# iWoofer_V4_03_OT.net
KiCad netlist of a schematic drawn in Altium Designer
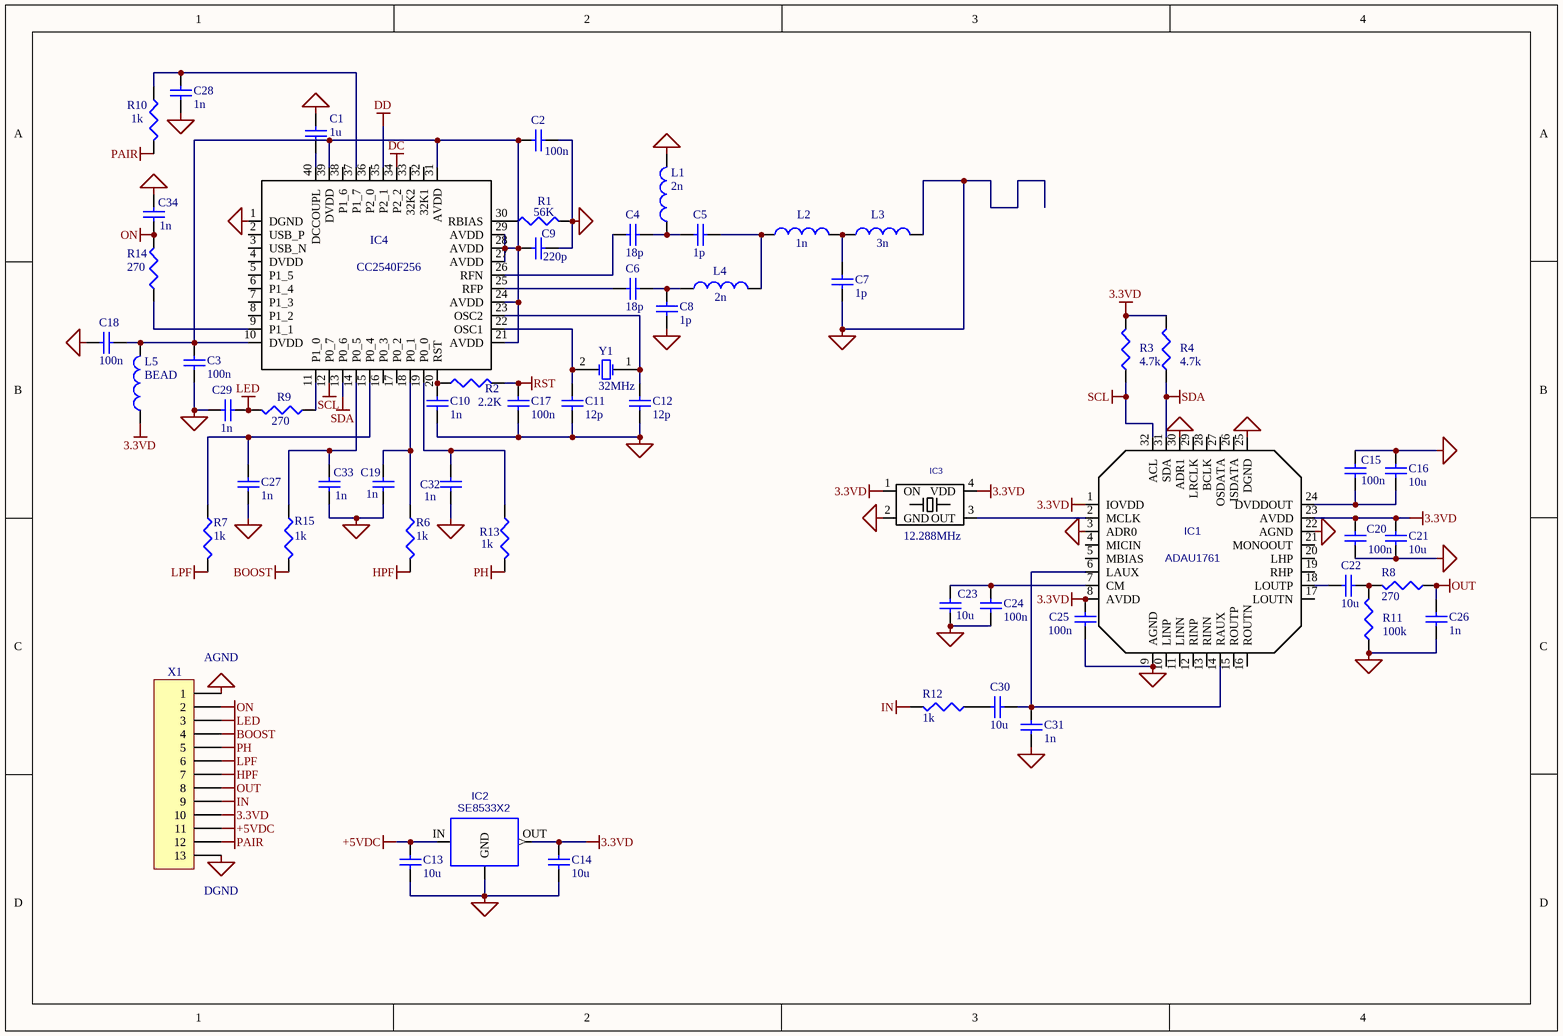
[diagram p0: iWoofer_V4_03_OT.SchDoc]

(export (version "E")
  (design (tool "Eeschema 10.0.6"))
  (components
    (comp (ref "C1")
      (value "1u")
      (footprint "0402C")
      (description "Capacitor")
      (fields (field (name "PUBLISHER") "Altium Limited"))
      (libsource (lib "vic_2") (part "Cap"))
    )
    (comp (ref "C2")
      (value "100n")
      (footprint "0402C")
      (description "Capacitor")
      (fields (field (name "PUBLISHER") "Altium Limited"))
      (libsource (lib "vic_2") (part "Cap"))
    )
    (comp (ref "C3")
      (value "100n")
      (footprint "0402C")
      (description "Capacitor")
      (fields (field (name "PUBLISHER") "Altium Limited"))
      (libsource (lib "vic_2") (part "Cap"))
    )
    (comp (ref "C4")
      (value "18p")
      (footprint "0402C")
      (description "Capacitor NPO")
      (fields (field (name "PUBLISHER") "Altium Limited"))
      (libsource (lib "vic_2") (part "Cap"))
    )
    (comp (ref "C5")
      (value "1p")
      (footprint "0402C")
      (description "Capacitor NPO")
      (fields (field (name "PUBLISHER") "Altium Limited"))
      (libsource (lib "vic_2") (part "Cap"))
    )
    (comp (ref "C6")
      (value "18p")
      (footprint "0402C")
      (description "Capacitor NPO")
      (fields (field (name "PUBLISHER") "Altium Limited"))
      (libsource (lib "vic_2") (part "Cap"))
    )
    (comp (ref "C7")
      (value "1p")
      (footprint "0402C")
      (description "Capacitor NPO")
      (fields (field (name "PUBLISHER") "Altium Limited"))
      (libsource (lib "vic_2") (part "Cap"))
    )
    (comp (ref "C8")
      (value "1p")
      (footprint "0402C")
      (description "Capacitor NPO")
      (fields (field (name "PUBLISHER") "Altium Limited"))
      (libsource (lib "vic_2") (part "Cap"))
    )
    (comp (ref "C9")
      (value "220p")
      (footprint "0402C")
      (description "Capacitor NPO")
      (fields (field (name "PUBLISHER") "Altium Limited"))
      (libsource (lib "vic_2") (part "Cap"))
    )
    (comp (ref "C10")
      (value "1n")
      (footprint "0402C")
      (description "Capacitor")
      (fields (field (name "PUBLISHER") "Altium Limited"))
      (libsource (lib "vic_2") (part "Cap"))
    )
    (comp (ref "C11")
      (value "12p")
      (footprint "0402C")
      (description "Capacitor NPO")
      (fields (field (name "PUBLISHER") "Altium Limited"))
      (libsource (lib "vic_2") (part "Cap"))
    )
    (comp (ref "C12")
      (value "12p")
      (footprint "0402C")
      (description "Capacitor NPO")
      (fields (field (name "PUBLISHER") "Altium Limited"))
      (libsource (lib "vic_2") (part "Cap"))
    )
    (comp (ref "C13")
      (value "10u")
      (footprint "0805C")
      (description "CL21A476MQMNRN or analog")
      (fields (field (name "PUBLISHER") "Altium Limited"))
      (libsource (lib "vic_2") (part "Cap"))
    )
    (comp (ref "C14")
      (value "10u")
      (footprint "0805C")
      (description "CL21A476MQMNRN or analog")
      (fields (field (name "PUBLISHER") "Altium Limited"))
      (libsource (lib "vic_2") (part "Cap"))
    )
    (comp (ref "C15")
      (value "100n")
      (footprint "0402C")
      (description "Capacitor")
      (fields (field (name "PUBLISHER") "Altium Limited"))
      (libsource (lib "vic_2") (part "Cap"))
    )
    (comp (ref "C16")
      (value "10u")
      (footprint "0805C")
      (description "CL21A476MQMNRN or analog")
      (fields (field (name "PUBLISHER") "Altium Limited"))
      (libsource (lib "vic_2") (part "Cap"))
    )
    (comp (ref "C17")
      (value "100n")
      (footprint "0402C")
      (description "Capacitor")
      (fields (field (name "PUBLISHER") "Altium Limited"))
      (libsource (lib "vic_2") (part "Cap"))
    )
    (comp (ref "C18")
      (value "100n")
      (footprint "0402C")
      (description "Capacitor")
      (fields (field (name "PUBLISHER") "Altium Limited"))
      (libsource (lib "vic_2") (part "Cap"))
    )
    (comp (ref "C19")
      (value "1n")
      (footprint "0402C")
      (description "Capacitor")
      (fields (field (name "PUBLISHER") "Altium Limited"))
      (libsource (lib "vic_2") (part "Cap"))
    )
    (comp (ref "C20")
      (value "100n")
      (footprint "0402C")
      (description "Capacitor")
      (fields (field (name "PUBLISHER") "Altium Limited"))
      (libsource (lib "vic_2") (part "Cap"))
    )
    (comp (ref "C21")
      (value "10u")
      (footprint "0805C")
      (description "CL21A476MQMNRN or analog")
      (fields (field (name "PUBLISHER") "Altium Limited"))
      (libsource (lib "vic_2") (part "Cap"))
    )
    (comp (ref "C22")
      (value "10u")
      (footprint "0805C")
      (description "CL21A476MQMNRN or analog")
      (fields (field (name "PUBLISHER") "Altium Limited"))
      (libsource (lib "vic_2") (part "Cap"))
    )
    (comp (ref "C23")
      (value "10u")
      (footprint "0805C")
      (description "CL21A476MQMNRN or analog")
      (fields (field (name "PUBLISHER") "Altium Limited"))
      (libsource (lib "vic_2") (part "Cap"))
    )
    (comp (ref "C24")
      (value "100n")
      (footprint "0402C")
      (description "Capacitor")
      (fields (field (name "PUBLISHER") "Altium Limited"))
      (libsource (lib "vic_2") (part "Cap"))
    )
    (comp (ref "C25")
      (value "100n")
      (footprint "0603")
      (description "Capacitor")
      (fields (field (name "PUBLISHER") "Altium Limited"))
      (libsource (lib "vic_2") (part "Cap"))
    )
    (comp (ref "C26")
      (value "1n")
      (footprint "0402C")
      (description "Capacitor")
      (fields (field (name "PUBLISHER") "Altium Limited"))
      (libsource (lib "vic_2") (part "Cap"))
    )
    (comp (ref "C27")
      (value "1n")
      (footprint "0402C")
      (description "Capacitor")
      (fields (field (name "PUBLISHER") "Altium Limited"))
      (libsource (lib "vic_2") (part "Cap"))
    )
    (comp (ref "C28")
      (value "1n")
      (footprint "0402C")
      (description "Capacitor")
      (fields (field (name "PUBLISHER") "Altium Limited"))
      (libsource (lib "vic_2") (part "Cap"))
    )
    (comp (ref "C29")
      (value "1n")
      (footprint "0402C")
      (description "Capacitor")
      (fields (field (name "PUBLISHER") "Altium Limited"))
      (libsource (lib "vic_2") (part "Cap"))
    )
    (comp (ref "C30")
      (value "10u")
      (footprint "0805C")
      (description "CL21A476MQMNRN or analog")
      (fields (field (name "PUBLISHER") "Altium Limited"))
      (libsource (lib "vic_2") (part "Cap"))
    )
    (comp (ref "C31")
      (value "1n")
      (footprint "0402C")
      (description "Capacitor")
      (fields (field (name "PUBLISHER") "Altium Limited"))
      (libsource (lib "vic_2") (part "Cap"))
    )
    (comp (ref "C32")
      (value "1n")
      (footprint "0402C")
      (description "Capacitor")
      (fields (field (name "PUBLISHER") "Altium Limited"))
      (libsource (lib "vic_2") (part "Cap"))
    )
    (comp (ref "C33")
      (value "1n")
      (footprint "0402C")
      (description "Capacitor")
      (fields (field (name "PUBLISHER") "Altium Limited"))
      (libsource (lib "vic_2") (part "Cap"))
    )
    (comp (ref "C34")
      (value "1n")
      (footprint "0402C")
      (description "Capacitor")
      (fields (field (name "PUBLISHER") "Altium Limited"))
      (libsource (lib "vic_2") (part "Cap"))
    )
    (comp (ref "IC1")
      (value "ADAU1761")
      (footprint "ADAU1761_long")
      (description "DSP")
      (libsource (lib "1") (part "ADAU1761"))
    )
    (comp (ref "IC2")
      (value "SE8533X2")
      (footprint "SOT-23_BC807-40(Primary)")
      (description "REGULATOR")
      (libsource (lib "1") (part "78L05"))
    )
    (comp (ref "IC3")
      (value "12.288 MHz")
      (footprint "OSC_3225")
      (description "12.288 MHz Oscillator 5032 case")
      (libsource (lib "1") (part "YSO 321SR"))
    )
    (comp (ref "IC4")
      (value "CC2540F256")
      (footprint "cc2540 TOP")
      (description "cc2540f256")
      (libsource (lib "1") (part "CC2540"))
    )
    (comp (ref "L1")
      (value "2n")
      (footprint "0402L")
      (description "HBLS1005-2N0S")
      (fields (field (name "PUBLISHER") "Altium Limited"))
      (libsource (lib "Miscellaneous Devices") (part "Inductor"))
    )
    (comp (ref "L2")
      (value "1n")
      (footprint "0402L")
      (description "HBLS1005-1N0S")
      (fields (field (name "PUBLISHER") "Altium Limited"))
      (libsource (lib "Miscellaneous Devices") (part "Inductor"))
    )
    (comp (ref "L3")
      (value "3n")
      (footprint "0402L")
      (description "HBLS1005-3N0S")
      (fields (field (name "PUBLISHER") "Altium Limited"))
      (libsource (lib "Miscellaneous Devices") (part "Inductor"))
    )
    (comp (ref "L4")
      (value "2n")
      (footprint "0402L")
      (description "HBLS1005-2N0S")
      (fields (field (name "PUBLISHER") "Altium Limited"))
      (libsource (lib "Miscellaneous Devices") (part "Inductor"))
    )
    (comp (ref "L5")
      (value "BEAD")
      (footprint "0402L")
      (description "bead 200@100MHz")
      (fields (field (name "PUBLISHER") "Altium Limited"))
      (libsource (lib "Miscellaneous Devices") (part "Inductor"))
    )
    (comp (ref "R1")
      (value "56K")
      (footprint "0402R")
      (description "Resistor")
      (fields (field (name "PUBLISHER") "Altium Limited"))
      (libsource (lib "vic_2") (part "Res3"))
    )
    (comp (ref "R2")
      (value "2.2K")
      (footprint "0402R")
      (description "Resistor")
      (fields (field (name "PUBLISHER") "Altium Limited"))
      (libsource (lib "vic_2") (part "Res3"))
    )
    (comp (ref "R3")
      (value "4.7k")
      (footprint "0402R")
      (description "Resistor")
      (fields (field (name "PUBLISHER") "Altium Limited"))
      (libsource (lib "vic_2") (part "Res3"))
    )
    (comp (ref "R4")
      (value "4.7k")
      (footprint "0402R")
      (description "Resistor")
      (fields (field (name "PUBLISHER") "Altium Limited"))
      (libsource (lib "vic_2") (part "Res3"))
    )
    (comp (ref "R6")
      (value "1k")
      (footprint "0402R")
      (description "Resistor")
      (fields (field (name "PUBLISHER") "Altium Limited"))
      (libsource (lib "vic_2") (part "Res3"))
    )
    (comp (ref "R7")
      (value "1k")
      (footprint "0402R")
      (description "Resistor")
      (fields (field (name "PUBLISHER") "Altium Limited"))
      (libsource (lib "vic_2") (part "Res3"))
    )
    (comp (ref "R8")
      (value "270")
      (footprint "0402R")
      (description "Resistor")
      (fields (field (name "PUBLISHER") "Altium Limited"))
      (libsource (lib "vic_2") (part "Res3"))
    )
    (comp (ref "R9")
      (value "270")
      (footprint "0402R")
      (description "Resistor")
      (fields (field (name "PUBLISHER") "Altium Limited"))
      (libsource (lib "vic_2") (part "Res3"))
    )
    (comp (ref "R10")
      (value "1k")
      (footprint "0402R")
      (description "Resistor")
      (fields (field (name "PUBLISHER") "Altium Limited"))
      (libsource (lib "vic_2") (part "Res3"))
    )
    (comp (ref "R11")
      (value "100k")
      (footprint "0402R")
      (description "Resistor")
      (fields (field (name "PUBLISHER") "Altium Limited"))
      (libsource (lib "vic_2") (part "Res3"))
    )
    (comp (ref "R12")
      (value "1k")
      (footprint "0402R")
      (description "Resistor")
      (fields (field (name "PUBLISHER") "Altium Limited"))
      (libsource (lib "vic_2") (part "Res3"))
    )
    (comp (ref "R13")
      (value "1k")
      (footprint "0402R")
      (description "Resistor")
      (fields (field (name "PUBLISHER") "Altium Limited"))
      (libsource (lib "vic_2") (part "Res3"))
    )
    (comp (ref "R14")
      (value "270")
      (footprint "0402R")
      (description "Resistor")
      (fields (field (name "PUBLISHER") "Altium Limited"))
      (libsource (lib "vic_2") (part "Res3"))
    )
    (comp (ref "R15")
      (value "1k")
      (footprint "0402R")
      (description "Resistor")
      (fields (field (name "PUBLISHER") "Altium Limited"))
      (libsource (lib "vic_2") (part "Res3"))
    )
    (comp (ref "X1")
      (value "Header 13")
      (footprint "HDR1X13")
      (description "Header, 13-Pin")
      (fields (field (name "PUBLISHER") "Altium Limited"))
      (libsource (lib "Miscellaneous Connectors") (part "Header 13"))
    )
    (comp (ref "Y1")
      (value "32MHz")
      (footprint "OSC_3225")
      (description "Crystal 3225 case 10ppm")
      (fields (field (name "PUBLISHER") "Altium Limited"))
      (libsource (lib "Miscellaneous Devices") (part "XTAL"))
    )
  )
  (nets
    (net (code "1") (name "+5VDC") (class "Default")
      (node (ref "C13") (pin "2") (pinfunction "2_2") (pintype "passive"))
      (node (ref "IC2") (pin "IN") (pinfunction "IN_IN") (pintype "power_in"))
      (node (ref "X1") (pin "11") (pinfunction "11_11") (pintype "passive"))
    )
    (net (code "2") (name "3.3VD") (class "Default")
      (node (ref "C14") (pin "2") (pinfunction "2_2") (pintype "passive"))
      (node (ref "C20") (pin "2") (pinfunction "2_2") (pintype "passive"))
      (node (ref "C21") (pin "2") (pinfunction "2_2") (pintype "passive"))
      (node (ref "C25") (pin "2") (pinfunction "2_2") (pintype "passive"))
      (node (ref "IC1") (pin "1") (pinfunction "IOVDD_1") (pintype "power_in"))
      (node (ref "IC1") (pin "23") (pinfunction "AVDD_23") (pintype "power_in"))
      (node (ref "IC1") (pin "8") (pinfunction "AVDD_8") (pintype "power_in"))
      (node (ref "IC2") (pin "OUT") (pinfunction "OUT_OUT") (pintype "output"))
      (node (ref "IC3") (pin "1") (pinfunction "ON_1") (pintype "passive"))
      (node (ref "IC3") (pin "4") (pinfunction "VDD_4") (pintype "passive"))
      (node (ref "L5") (pin "1") (pinfunction "1_1") (pintype "passive"))
      (node (ref "R3") (pin "2") (pinfunction "2_2") (pintype "passive"))
      (node (ref "R4") (pin "2") (pinfunction "2_2") (pintype "passive"))
      (node (ref "X1") (pin "10") (pinfunction "10_10") (pintype "passive"))
    )
    (net (code "3") (name "BOOST") (class "Default")
      (node (ref "R15") (pin "2") (pinfunction "2_2") (pintype "passive"))
      (node (ref "X1") (pin "4") (pinfunction "4_4") (pintype "passive"))
    )
    (net (code "4") (name "DC") (class "Default")
      (node (ref "IC4") (pin "34") (pinfunction "P2_2_34") (pintype "power_in"))
    )
    (net (code "5") (name "DD") (class "Default")
      (node (ref "IC4") (pin "35") (pinfunction "P2_1_35") (pintype "power_in"))
    )
    (net (code "6") (name "GND") (class "Default")
      (node (ref "C1") (pin "2") (pinfunction "2_2") (pintype "passive"))
      (node (ref "C10") (pin "1") (pinfunction "1_1") (pintype "passive"))
      (node (ref "C11") (pin "1") (pinfunction "1_1") (pintype "passive"))
      (node (ref "C12") (pin "1") (pinfunction "1_1") (pintype "passive"))
      (node (ref "C13") (pin "1") (pinfunction "1_1") (pintype "passive"))
      (node (ref "C14") (pin "1") (pinfunction "1_1") (pintype "passive"))
      (node (ref "C15") (pin "2") (pinfunction "2_2") (pintype "passive"))
      (node (ref "C16") (pin "2") (pinfunction "2_2") (pintype "passive"))
      (node (ref "C17") (pin "2") (pinfunction "2_2") (pintype "passive"))
      (node (ref "C18") (pin "1") (pinfunction "1_1") (pintype "passive"))
      (node (ref "C19") (pin "2") (pinfunction "2_2") (pintype "passive"))
      (node (ref "C2") (pin "1") (pinfunction "1_1") (pintype "passive"))
      (node (ref "C20") (pin "1") (pinfunction "1_1") (pintype "passive"))
      (node (ref "C21") (pin "1") (pinfunction "1_1") (pintype "passive"))
      (node (ref "C23") (pin "1") (pinfunction "1_1") (pintype "passive"))
      (node (ref "C24") (pin "1") (pinfunction "1_1") (pintype "passive"))
      (node (ref "C25") (pin "1") (pinfunction "1_1") (pintype "passive"))
      (node (ref "C26") (pin "1") (pinfunction "1_1") (pintype "passive"))
      (node (ref "C27") (pin "1") (pinfunction "1_1") (pintype "passive"))
      (node (ref "C28") (pin "1") (pinfunction "1_1") (pintype "passive"))
      (node (ref "C29") (pin "1") (pinfunction "1_1") (pintype "passive"))
      (node (ref "C3") (pin "1") (pinfunction "1_1") (pintype "passive"))
      (node (ref "C31") (pin "1") (pinfunction "1_1") (pintype "passive"))
      (node (ref "C32") (pin "1") (pinfunction "1_1") (pintype "passive"))
      (node (ref "C33") (pin "1") (pinfunction "1_1") (pintype "passive"))
      (node (ref "C34") (pin "2") (pinfunction "2_2") (pintype "passive"))
      (node (ref "C7") (pin "2") (pinfunction "2_2") (pintype "passive"))
      (node (ref "C8") (pin "2") (pinfunction "2_2") (pintype "passive"))
      (node (ref "C9") (pin "2") (pinfunction "2_2") (pintype "passive"))
      (node (ref "IC1") (pin "22") (pinfunction "AGND_22") (pintype "power_in"))
      (node (ref "IC1") (pin "25") (pinfunction "DGND_25") (pintype "power_in"))
      (node (ref "IC1") (pin "3") (pinfunction "ADR0_3") (pintype "power_in"))
      (node (ref "IC1") (pin "30") (pinfunction "ADR1_30") (pintype "power_in"))
      (node (ref "IC1") (pin "9") (pinfunction "AGND_9") (pintype "power_in"))
      (node (ref "IC2") (pin "GND") (pinfunction "GND_GND") (pintype "power_in"))
      (node (ref "IC3") (pin "2") (pinfunction "GND_2") (pintype "passive"))
      (node (ref "IC4") (pin "1") (pinfunction "DGND_1") (pintype "power_in"))
      (node (ref "L1") (pin "2") (pinfunction "2_2") (pintype "passive"))
      (node (ref "L3") (pin "2") (pinfunction "2_2") (pintype "passive"))
      (node (ref "R1") (pin "2") (pinfunction "2_2") (pintype "passive"))
      (node (ref "R11") (pin "1") (pinfunction "1_1") (pintype "passive"))
      (node (ref "X1") (pin "1") (pinfunction "1_1") (pintype "passive"))
      (node (ref "X1") (pin "13") (pinfunction "13_13") (pintype "passive"))
    )
    (net (code "7") (name "HPF") (class "Default")
      (node (ref "R6") (pin "2") (pinfunction "2_2") (pintype "passive"))
      (node (ref "X1") (pin "7") (pinfunction "7_7") (pintype "passive"))
    )
    (net (code "8") (name "IN") (class "Default")
      (node (ref "R12") (pin "2") (pinfunction "2_2") (pintype "passive"))
      (node (ref "X1") (pin "9") (pinfunction "9_9") (pintype "passive"))
    )
    (net (code "9") (name "LED") (class "Default")
      (node (ref "C29") (pin "2") (pinfunction "2_2") (pintype "passive"))
      (node (ref "R9") (pin "2") (pinfunction "2_2") (pintype "passive"))
      (node (ref "X1") (pin "3") (pinfunction "3_3") (pintype "passive"))
    )
    (net (code "10") (name "LPF") (class "Default")
      (node (ref "R7") (pin "2") (pinfunction "2_2") (pintype "passive"))
      (node (ref "X1") (pin "6") (pinfunction "6_6") (pintype "passive"))
    )
    (net (code "11") (name "Net-(C4-Pad1)") (class "Default")
      (node (ref "C4") (pin "1") (pinfunction "1_1") (pintype "passive"))
      (node (ref "C5") (pin "2") (pinfunction "2_2") (pintype "passive"))
      (node (ref "L1") (pin "1") (pinfunction "1_1") (pintype "passive"))
    )
    (net (code "12") (name "Net-(C5-Pad1)") (class "Default")
      (node (ref "C5") (pin "1") (pinfunction "1_1") (pintype "passive"))
      (node (ref "L2") (pin "1") (pinfunction "1_1") (pintype "passive"))
      (node (ref "L4") (pin "2") (pinfunction "2_2") (pintype "passive"))
    )
    (net (code "13") (name "Net-(C6-Pad1)") (class "Default")
      (node (ref "C6") (pin "1") (pinfunction "1_1") (pintype "passive"))
      (node (ref "C8") (pin "1") (pinfunction "1_1") (pintype "passive"))
      (node (ref "L4") (pin "1") (pinfunction "1_1") (pintype "passive"))
    )
    (net (code "14") (name "Net-(C7-Pad1)") (class "Default")
      (node (ref "C7") (pin "1") (pinfunction "1_1") (pintype "passive"))
      (node (ref "L2") (pin "2") (pinfunction "2_2") (pintype "passive"))
      (node (ref "L3") (pin "1") (pinfunction "1_1") (pintype "passive"))
    )
    (net (code "15") (name "Net-(C18-Pad2)") (class "Default")
      (node (ref "C18") (pin "2") (pinfunction "2_2") (pintype "passive"))
      (node (ref "C2") (pin "2") (pinfunction "2_2") (pintype "passive"))
      (node (ref "C3") (pin "2") (pinfunction "2_2") (pintype "passive"))
      (node (ref "C9") (pin "1") (pinfunction "1_1") (pintype "passive"))
      (node (ref "IC4") (pin "10") (pinfunction "DVDD_10") (pintype "power_in"))
      (node (ref "IC4") (pin "21") (pinfunction "AVDD_21") (pintype "power_in"))
      (node (ref "IC4") (pin "24") (pinfunction "AVDD_24") (pintype "power_in"))
      (node (ref "IC4") (pin "27") (pinfunction "AVDD_27") (pintype "power_in"))
      (node (ref "IC4") (pin "28") (pinfunction "AVDD_28") (pintype "power_in"))
      (node (ref "IC4") (pin "29") (pinfunction "AVDD_29") (pintype "power_in"))
      (node (ref "IC4") (pin "31") (pinfunction "AVDD_31") (pintype "power_in"))
      (node (ref "IC4") (pin "39") (pinfunction "DVDD_39") (pintype "power_in"))
      (node (ref "L5") (pin "2") (pinfunction "2_2") (pintype "passive"))
    )
    (net (code "16") (name "Net-(C22-Pad2)") (class "Default")
      (node (ref "C22") (pin "2") (pinfunction "2_2") (pintype "passive"))
      (node (ref "R11") (pin "2") (pinfunction "2_2") (pintype "passive"))
      (node (ref "R8") (pin "2") (pinfunction "2_2") (pintype "passive"))
    )
    (net (code "17") (name "Net-(C30-Pad1)") (class "Default")
      (node (ref "C30") (pin "1") (pinfunction "1_1") (pintype "passive"))
      (node (ref "R12") (pin "1") (pinfunction "1_1") (pintype "passive"))
    )
    (net (code "18") (name "Net-(IC1-CM)") (class "Default")
      (node (ref "C23") (pin "2") (pinfunction "2_2") (pintype "passive"))
      (node (ref "C24") (pin "2") (pinfunction "2_2") (pintype "passive"))
      (node (ref "IC1") (pin "7") (pinfunction "CM_7") (pintype "power_in"))
    )
    (net (code "19") (name "Net-(IC1-DVDDOUT)") (class "Default")
      (node (ref "C15") (pin "1") (pinfunction "1_1") (pintype "passive"))
      (node (ref "C16") (pin "1") (pinfunction "1_1") (pintype "passive"))
      (node (ref "IC1") (pin "24") (pinfunction "DVDDOUT_24") (pintype "power_in"))
    )
    (net (code "20") (name "Net-(IC1-LAUX)") (class "Default")
      (node (ref "C30") (pin "2") (pinfunction "2_2") (pintype "passive"))
      (node (ref "C31") (pin "2") (pinfunction "2_2") (pintype "passive"))
      (node (ref "IC1") (pin "14") (pinfunction "RAUX_14") (pintype "power_in"))
      (node (ref "IC1") (pin "6") (pinfunction "LAUX_6") (pintype "power_in"))
    )
    (net (code "21") (name "Net-(IC1-LOUTP)") (class "Default")
      (node (ref "C22") (pin "1") (pinfunction "1_1") (pintype "passive"))
      (node (ref "IC1") (pin "18") (pinfunction "LOUTP_18") (pintype "power_in"))
    )
    (net (code "22") (name "Net-(IC1-MCLK)") (class "Default")
      (node (ref "IC1") (pin "2") (pinfunction "MCLK_2") (pintype "power_in"))
      (node (ref "IC3") (pin "3") (pinfunction "OUT_3") (pintype "passive"))
    )
    (net (code "23") (name "Net-(IC4-DCCOUPL)") (class "Default")
      (node (ref "C1") (pin "1") (pinfunction "1_1") (pintype "passive"))
      (node (ref "IC4") (pin "40") (pinfunction "DCCOUPL_40") (pintype "power_in"))
    )
    (net (code "24") (name "Net-(IC4-OSC1)") (class "Default")
      (node (ref "C11") (pin "2") (pinfunction "2_2") (pintype "passive"))
      (node (ref "IC4") (pin "22") (pinfunction "OSC1_22") (pintype "power_in"))
      (node (ref "Y1") (pin "2") (pinfunction "OSC2_2") (pintype "passive"))
    )
    (net (code "25") (name "Net-(IC4-OSC2)") (class "Default")
      (node (ref "C12") (pin "2") (pinfunction "2_2") (pintype "passive"))
      (node (ref "IC4") (pin "23") (pinfunction "OSC2_23") (pintype "power_in"))
      (node (ref "Y1") (pin "1") (pinfunction "OSC1_1") (pintype "passive"))
    )
    (net (code "26") (name "Net-(IC4-P0_0)") (class "Default")
      (node (ref "C32") (pin "2") (pinfunction "2_2") (pintype "passive"))
      (node (ref "IC4") (pin "19") (pinfunction "P0_0_19") (pintype "power_in"))
      (node (ref "R13") (pin "1") (pinfunction "1_1") (pintype "passive"))
    )
    (net (code "27") (name "Net-(IC4-P0_1)") (class "Default")
      (node (ref "C19") (pin "1") (pinfunction "1_1") (pintype "passive"))
      (node (ref "IC4") (pin "18") (pinfunction "P0_1_18") (pintype "power_in"))
      (node (ref "R6") (pin "1") (pinfunction "1_1") (pintype "passive"))
    )
    (net (code "28") (name "Net-(IC4-P0_4)") (class "Default")
      (node (ref "C27") (pin "2") (pinfunction "2_2") (pintype "passive"))
      (node (ref "IC4") (pin "15") (pinfunction "P0_4_15") (pintype "power_in"))
      (node (ref "R7") (pin "1") (pinfunction "1_1") (pintype "passive"))
    )
    (net (code "29") (name "Net-(IC4-P0_5)") (class "Default")
      (node (ref "C33") (pin "2") (pinfunction "2_2") (pintype "passive"))
      (node (ref "IC4") (pin "14") (pinfunction "P0_5_14") (pintype "power_in"))
      (node (ref "R15") (pin "1") (pinfunction "1_1") (pintype "passive"))
    )
    (net (code "30") (name "Net-(IC4-P1_0)") (class "Default")
      (node (ref "IC4") (pin "11") (pinfunction "P1_0_11") (pintype "power_in"))
      (node (ref "R9") (pin "1") (pinfunction "1_1") (pintype "passive"))
    )
    (net (code "31") (name "Net-(IC4-P1_1)") (class "Default")
      (node (ref "IC4") (pin "9") (pinfunction "P1_1_9") (pintype "power_in"))
      (node (ref "R14") (pin "1") (pinfunction "1_1") (pintype "passive"))
    )
    (net (code "32") (name "Net-(IC4-P1_7)") (class "Default")
      (node (ref "C28") (pin "2") (pinfunction "2_2") (pintype "passive"))
      (node (ref "IC4") (pin "37") (pinfunction "P1_7_37") (pintype "power_in"))
      (node (ref "R10") (pin "1") (pinfunction "1_1") (pintype "passive"))
    )
    (net (code "33") (name "Net-(IC4-RBIAS)") (class "Default")
      (node (ref "IC4") (pin "30") (pinfunction "RBIAS_30") (pintype "power_in"))
      (node (ref "R1") (pin "1") (pinfunction "1_1") (pintype "passive"))
    )
    (net (code "34") (name "Net-(IC4-RFN)") (class "Default")
      (node (ref "C4") (pin "2") (pinfunction "2_2") (pintype "passive"))
      (node (ref "IC4") (pin "26") (pinfunction "RFN_26") (pintype "power_in"))
    )
    (net (code "35") (name "Net-(IC4-RFP)") (class "Default")
      (node (ref "C6") (pin "2") (pinfunction "2_2") (pintype "passive"))
      (node (ref "IC4") (pin "25") (pinfunction "RFP_25") (pintype "power_in"))
    )
    (net (code "36") (name "Net-(IC4-RST)") (class "Default")
      (node (ref "C10") (pin "2") (pinfunction "2_2") (pintype "passive"))
      (node (ref "IC4") (pin "20") (pinfunction "RST_20") (pintype "power_in"))
      (node (ref "R2") (pin "1") (pinfunction "1_1") (pintype "passive"))
    )
    (net (code "37") (name "ON") (class "Default")
      (node (ref "C34") (pin "1") (pinfunction "1_1") (pintype "passive"))
      (node (ref "R14") (pin "2") (pinfunction "2_2") (pintype "passive"))
      (node (ref "X1") (pin "2") (pinfunction "2_2") (pintype "passive"))
    )
    (net (code "38") (name "OUT") (class "Default")
      (node (ref "C26") (pin "2") (pinfunction "2_2") (pintype "passive"))
      (node (ref "R8") (pin "1") (pinfunction "1_1") (pintype "passive"))
      (node (ref "X1") (pin "8") (pinfunction "8_8") (pintype "passive"))
    )
    (net (code "39") (name "PAIR") (class "Default")
      (node (ref "R10") (pin "2") (pinfunction "2_2") (pintype "passive"))
      (node (ref "X1") (pin "12") (pinfunction "12_12") (pintype "passive"))
    )
    (net (code "40") (name "PH") (class "Default")
      (node (ref "R13") (pin "2") (pinfunction "2_2") (pintype "passive"))
      (node (ref "X1") (pin "5") (pinfunction "5_5") (pintype "passive"))
    )
    (net (code "41") (name "RST") (class "Default")
      (node (ref "C17") (pin "1") (pinfunction "1_1") (pintype "passive"))
      (node (ref "R2") (pin "2") (pinfunction "2_2") (pintype "passive"))
    )
    (net (code "42") (name "SCL") (class "Default")
      (node (ref "IC1") (pin "32") (pinfunction "ACL_32") (pintype "power_in"))
      (node (ref "IC4") (pin "12") (pinfunction "P0_7_12") (pintype "power_in"))
      (node (ref "R3") (pin "1") (pinfunction "1_1") (pintype "passive"))
    )
    (net (code "43") (name "SDA") (class "Default")
      (node (ref "IC1") (pin "31") (pinfunction "SDA_31") (pintype "power_in"))
      (node (ref "IC4") (pin "13") (pinfunction "P0_6_13") (pintype "power_in"))
      (node (ref "R4") (pin "1") (pinfunction "1_1") (pintype "passive"))
    )
    (net (code "44") (name "unconnected-(IC1-BCLK-Pad28)") (class "Default")
      (node (ref "IC1") (pin "28") (pinfunction "BCLK_28") (pintype "power_in"))
    )
    (net (code "45") (name "unconnected-(IC1-ISDATA-Pad26)") (class "Default")
      (node (ref "IC1") (pin "26") (pinfunction "ISDATA_26") (pintype "power_in"))
    )
    (net (code "46") (name "unconnected-(IC1-LHP-Pad20)") (class "Default")
      (node (ref "IC1") (pin "20") (pinfunction "LHP_20") (pintype "power_in"))
    )
    (net (code "47") (name "unconnected-(IC1-LINN-Pad11)") (class "Default")
      (node (ref "IC1") (pin "11") (pinfunction "LINN_11") (pintype "power_in"))
    )
    (net (code "48") (name "unconnected-(IC1-LINP-Pad10)") (class "Default")
      (node (ref "IC1") (pin "10") (pinfunction "LINP_10") (pintype "power_in"))
    )
    (net (code "49") (name "unconnected-(IC1-LOUTN-Pad17)") (class "Default")
      (node (ref "IC1") (pin "17") (pinfunction "LOUTN_17") (pintype "power_in"))
    )
    (net (code "50") (name "unconnected-(IC1-LRCLK-Pad29)") (class "Default")
      (node (ref "IC1") (pin "29") (pinfunction "LRCLK_29") (pintype "power_in"))
    )
    (net (code "51") (name "unconnected-(IC1-MBIAS-Pad5)") (class "Default")
      (node (ref "IC1") (pin "5") (pinfunction "MBIAS_5") (pintype "power_in"))
    )
    (net (code "52") (name "unconnected-(IC1-MICIN-Pad4)") (class "Default")
      (node (ref "IC1") (pin "4") (pinfunction "MICIN_4") (pintype "power_in"))
    )
    (net (code "53") (name "unconnected-(IC1-MONOOUT-Pad21)") (class "Default")
      (node (ref "IC1") (pin "21") (pinfunction "MONOOUT_21") (pintype "power_in"))
    )
    (net (code "54") (name "unconnected-(IC1-OSDATA-Pad27)") (class "Default")
      (node (ref "IC1") (pin "27") (pinfunction "OSDATA_27") (pintype "power_in"))
    )
    (net (code "55") (name "unconnected-(IC1-RHP-Pad19)") (class "Default")
      (node (ref "IC1") (pin "19") (pinfunction "RHP_19") (pintype "power_in"))
    )
    (net (code "56") (name "unconnected-(IC1-RINN-Pad13)") (class "Default")
      (node (ref "IC1") (pin "13") (pinfunction "RINN_13") (pintype "power_in"))
    )
    (net (code "57") (name "unconnected-(IC1-RINP-Pad12)") (class "Default")
      (node (ref "IC1") (pin "12") (pinfunction "RINP_12") (pintype "power_in"))
    )
    (net (code "58") (name "unconnected-(IC1-ROUTN-Pad16)") (class "Default")
      (node (ref "IC1") (pin "16") (pinfunction "ROUTN_16") (pintype "power_in"))
    )
    (net (code "59") (name "unconnected-(IC1-ROUTP-Pad15)") (class "Default")
      (node (ref "IC1") (pin "15") (pinfunction "ROUTP_15") (pintype "power_in"))
    )
    (net (code "60") (name "unconnected-(IC4-32K1-Pad32)") (class "Default")
      (node (ref "IC4") (pin "32") (pinfunction "32K1_32") (pintype "power_in"))
    )
    (net (code "61") (name "unconnected-(IC4-32K2-Pad33)") (class "Default")
      (node (ref "IC4") (pin "33") (pinfunction "32K2_33") (pintype "power_in"))
    )
    (net (code "62") (name "unconnected-(IC4-DVDD-Pad4)") (class "Default")
      (node (ref "IC4") (pin "4") (pinfunction "DVDD_4") (pintype "power_in"))
    )
    (net (code "63") (name "unconnected-(IC4-P0_2-Pad17)") (class "Default")
      (node (ref "IC4") (pin "17") (pinfunction "P0_2_17") (pintype "power_in"))
    )
    (net (code "64") (name "unconnected-(IC4-P0_3-Pad16)") (class "Default")
      (node (ref "IC4") (pin "16") (pinfunction "P0_3_16") (pintype "power_in"))
    )
    (net (code "65") (name "unconnected-(IC4-P1_2-Pad8)") (class "Default")
      (node (ref "IC4") (pin "8") (pinfunction "P1_2_8") (pintype "power_in"))
    )
    (net (code "66") (name "unconnected-(IC4-P1_3-Pad7)") (class "Default")
      (node (ref "IC4") (pin "7") (pinfunction "P1_3_7") (pintype "power_in"))
    )
    (net (code "67") (name "unconnected-(IC4-P1_4-Pad6)") (class "Default")
      (node (ref "IC4") (pin "6") (pinfunction "P1_4_6") (pintype "power_in"))
    )
    (net (code "68") (name "unconnected-(IC4-P1_5-Pad5)") (class "Default")
      (node (ref "IC4") (pin "5") (pinfunction "P1_5_5") (pintype "power_in"))
    )
    (net (code "69") (name "unconnected-(IC4-P1_6-Pad38)") (class "Default")
      (node (ref "IC4") (pin "38") (pinfunction "P1_6_38") (pintype "power_in"))
    )
    (net (code "70") (name "unconnected-(IC4-P2_0-Pad36)") (class "Default")
      (node (ref "IC4") (pin "36") (pinfunction "P2_0_36") (pintype "power_in"))
    )
    (net (code "71") (name "unconnected-(IC4-USB_N-Pad3)") (class "Default")
      (node (ref "IC4") (pin "3") (pinfunction "USB_N_3") (pintype "power_in"))
    )
    (net (code "72") (name "unconnected-(IC4-USB_P-Pad2)") (class "Default")
      (node (ref "IC4") (pin "2") (pinfunction "USB_P_2") (pintype "power_in"))
    )
  )
)
